# Spannungsversorgung-3.net
KiCad netlist of a schematic drawn in EAGLE
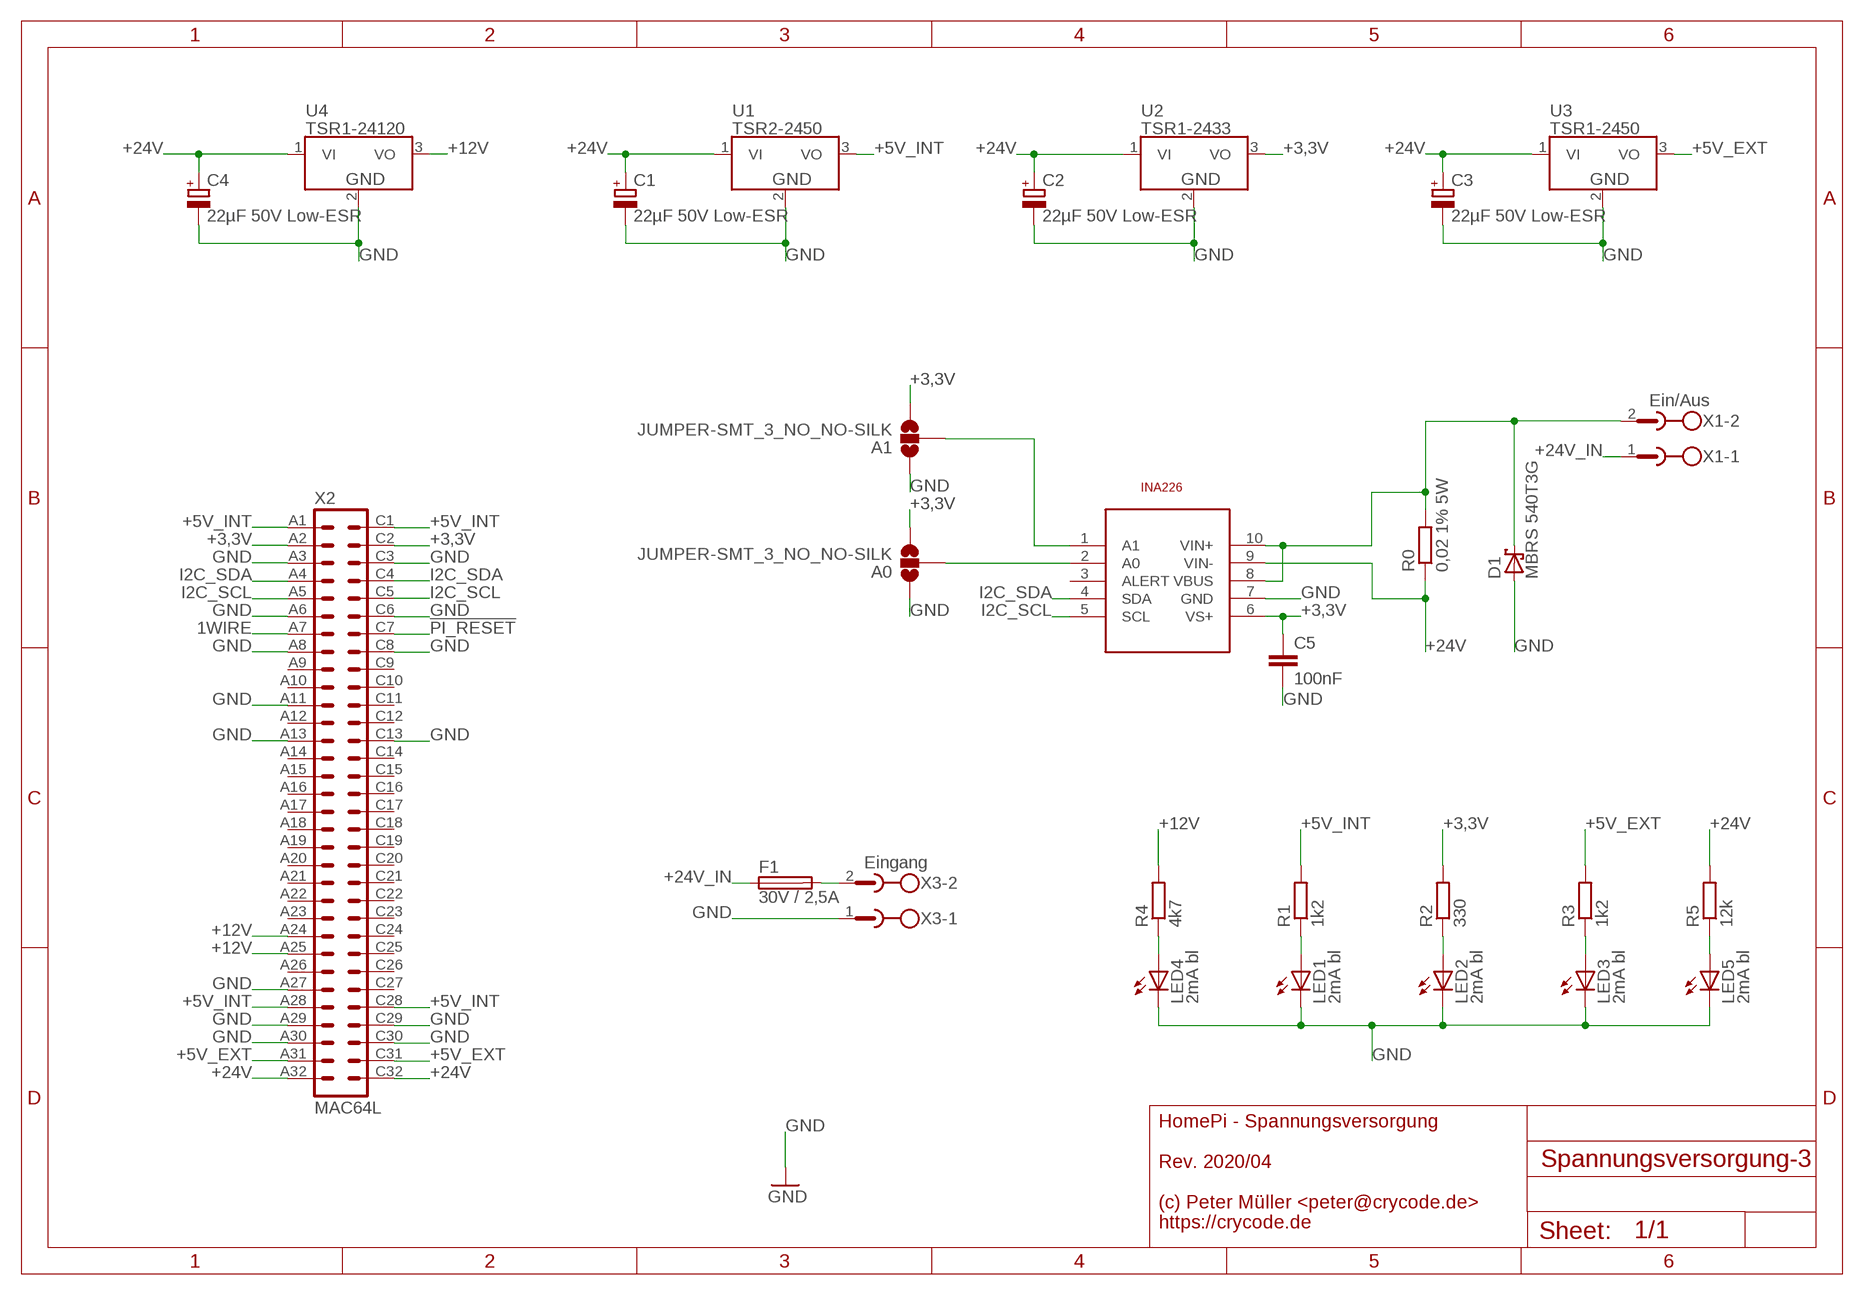
[diagram p0: schematic, sheet 1]

(export (version "E")
  (design (tool "Eeschema 10.0.6"))
  (components
    (comp (ref "A0")
      (value "JUMPER-SMT_3_NO_NO-SILK")
      (footprint "eagle-import:SMT-JUMPER_3_NO_NO-SILK")
      (libsource (lib "eagle-import") (part "JUMPER-SMT_3_NO_NO-SILK"))
    )
    (comp (ref "A1")
      (value "JUMPER-SMT_3_NO_NO-SILK")
      (footprint "eagle-import:SMT-JUMPER_3_NO_NO-SILK")
      (libsource (lib "eagle-import") (part "JUMPER-SMT_3_NO_NO-SILK"))
    )
    (comp (ref "C1")
      (value "22µF 50V Low-ESR")
      (footprint "eagle-import:E2-5")
      (libsource (lib "eagle-import") (part "CPOL-EUE2-5"))
    )
    (comp (ref "C2")
      (value "22µF 50V Low-ESR")
      (footprint "eagle-import:E2-5")
      (libsource (lib "eagle-import") (part "CPOL-EUE2-5"))
    )
    (comp (ref "C3")
      (value "22µF 50V Low-ESR")
      (footprint "eagle-import:E2-5")
      (libsource (lib "eagle-import") (part "CPOL-EUE2-5"))
    )
    (comp (ref "C4")
      (value "22µF 50V Low-ESR")
      (footprint "eagle-import:E2-5")
      (libsource (lib "eagle-import") (part "CPOL-EUE2-5"))
    )
    (comp (ref "C5")
      (value "100nF")
      (footprint "eagle-import:C1206")
      (libsource (lib "eagle-import") (part "C-EUC1206"))
    )
    (comp (ref "D1")
      (value "MBRS 540T3G")
      (footprint "eagle-import:SMC")
      (libsource (lib "eagle-import") (part "SCHOTTKY-DIODESMC"))
    )
    (comp (ref "F1")
      (value "30V / 2,5A")
      (footprint "eagle-import:LITTLEFUSE")
      (libsource (lib "eagle-import") (part "LITTLEFUSE"))
    )
    (comp (ref "IC1")
      (value "TI-INA226")
      (footprint "eagle-import:TI-INA226")
      (libsource (lib "eagle-import") (part "TI-INA226"))
    )
    (comp (ref "LED1")
      (value "2mA bl")
      (footprint "eagle-import:CHIPLED_1206")
      (libsource (lib "eagle-import") (part "LEDCHIPLED_1206"))
    )
    (comp (ref "LED2")
      (value "2mA bl")
      (footprint "eagle-import:CHIPLED_1206")
      (libsource (lib "eagle-import") (part "LEDCHIPLED_1206"))
    )
    (comp (ref "LED3")
      (value "2mA bl")
      (footprint "eagle-import:CHIPLED_1206")
      (libsource (lib "eagle-import") (part "LEDCHIPLED_1206"))
    )
    (comp (ref "LED4")
      (value "2mA bl")
      (footprint "eagle-import:CHIPLED_1206")
      (libsource (lib "eagle-import") (part "LEDCHIPLED_1206"))
    )
    (comp (ref "LED5")
      (value "2mA bl")
      (footprint "eagle-import:CHIPLED_1206")
      (libsource (lib "eagle-import") (part "LEDCHIPLED_1206"))
    )
    (comp (ref "R0")
      (value "0,02 1% 5W")
      (footprint "eagle-import:R2512")
      (libsource (lib "eagle-import") (part "R-EU_R2512"))
    )
    (comp (ref "R1")
      (value "1k2")
      (footprint "eagle-import:R1206")
      (libsource (lib "eagle-import") (part "R-EU_R1206"))
    )
    (comp (ref "R2")
      (value "330")
      (footprint "eagle-import:R1206")
      (libsource (lib "eagle-import") (part "R-EU_R1206"))
    )
    (comp (ref "R3")
      (value "1k2")
      (footprint "eagle-import:R1206")
      (libsource (lib "eagle-import") (part "R-EU_R1206"))
    )
    (comp (ref "R4")
      (value "4k7")
      (footprint "eagle-import:R1206")
      (libsource (lib "eagle-import") (part "R-EU_R1206"))
    )
    (comp (ref "R5")
      (value "12k")
      (footprint "eagle-import:R1206")
      (libsource (lib "eagle-import") (part "R-EU_R1206"))
    )
    (comp (ref "U1")
      (value "TSR2-2450")
      (footprint "eagle-import:TSR2")
      (libsource (lib "eagle-import") (part "TSR2-2450"))
    )
    (comp (ref "U2")
      (value "TSR1-2433")
      (footprint "eagle-import:TSR1")
      (libsource (lib "eagle-import") (part "TSR1-2433"))
    )
    (comp (ref "U3")
      (value "TSR1-2450")
      (footprint "eagle-import:TSR1")
      (libsource (lib "eagle-import") (part "TSR1-2450"))
    )
    (comp (ref "U4")
      (value "TSR1-24120")
      (footprint "eagle-import:TSR1")
      (libsource (lib "eagle-import") (part "TSR1-24120"))
    )
    (comp (ref "X1")
      (value "Ein/Aus")
      (footprint "eagle-import:MSTBA2")
      (fields (field (name "MF") "FARNELL") (field (name "MPN") "1757242"))
      (libsource (lib "eagle-import") (part "MSTBA2"))
    )
    (comp (ref "X2")
      (value "MAC64L")
      (footprint "eagle-import:MAC64L")
      (libsource (lib "eagle-import") (part "MAC64L"))
    )
    (comp (ref "X3")
      (value "Eingang")
      (footprint "eagle-import:MSTBA2")
      (fields (field (name "MF") "FARNELL") (field (name "MPN") "1757242"))
      (libsource (lib "eagle-import") (part "MSTBA2"))
    )
  )
  (nets
    (net (code "1") (name "/+3,3V") (class "Default")
      (node (ref "A0") (pin "3") (pinfunction "3_3") (pintype "passive"))
      (node (ref "A1") (pin "3") (pinfunction "3_3") (pintype "passive"))
      (node (ref "C5") (pin "1") (pinfunction "1_1") (pintype "passive"))
      (node (ref "IC1") (pin "6") (pinfunction "VS+_6") (pintype "bidirectional"))
      (node (ref "R2") (pin "2") (pinfunction "2_2") (pintype "passive"))
      (node (ref "U2") (pin "3") (pinfunction "VO_3") (pintype "power_in"))
      (node (ref "X2") (pin "A2") (pinfunction "A2_A2") (pintype "passive"))
      (node (ref "X2") (pin "C2") (pinfunction "C2_C2") (pintype "passive"))
    )
    (net (code "2") (name "/+5V_EXT") (class "Default")
      (node (ref "R3") (pin "2") (pinfunction "2_2") (pintype "passive"))
      (node (ref "U3") (pin "3") (pinfunction "VO_3") (pintype "power_in"))
      (node (ref "X2") (pin "A31") (pinfunction "A31_A31") (pintype "passive"))
      (node (ref "X2") (pin "C31") (pinfunction "C31_C31") (pintype "passive"))
    )
    (net (code "3") (name "/+5V_INT") (class "Default")
      (node (ref "R1") (pin "2") (pinfunction "2_2") (pintype "passive"))
      (node (ref "U1") (pin "3") (pinfunction "VO_3") (pintype "power_in"))
      (node (ref "X2") (pin "A1") (pinfunction "A1_A1") (pintype "passive"))
      (node (ref "X2") (pin "A28") (pinfunction "A28_A28") (pintype "passive"))
      (node (ref "X2") (pin "C1") (pinfunction "C1_C1") (pintype "passive"))
      (node (ref "X2") (pin "C28") (pinfunction "C28_C28") (pintype "passive"))
    )
    (net (code "4") (name "/+12V") (class "Default")
      (node (ref "R4") (pin "2") (pinfunction "2_2") (pintype "passive"))
      (node (ref "U4") (pin "3") (pinfunction "VO_3") (pintype "power_in"))
      (node (ref "X2") (pin "A24") (pinfunction "A24_A24") (pintype "passive"))
      (node (ref "X2") (pin "A25") (pinfunction "A25_A25") (pintype "passive"))
    )
    (net (code "5") (name "/+24V") (class "Default")
      (node (ref "C1") (pin "+") (pinfunction "+_+") (pintype "passive"))
      (node (ref "C2") (pin "+") (pinfunction "+_+") (pintype "passive"))
      (node (ref "C3") (pin "+") (pinfunction "+_+") (pintype "passive"))
      (node (ref "C4") (pin "+") (pinfunction "+_+") (pintype "passive"))
      (node (ref "IC1") (pin "9") (pinfunction "VIN-_9") (pintype "bidirectional"))
      (node (ref "R0") (pin "1") (pinfunction "1_1") (pintype "passive"))
      (node (ref "R5") (pin "2") (pinfunction "2_2") (pintype "passive"))
      (node (ref "U1") (pin "1") (pinfunction "VI_1") (pintype "power_in"))
      (node (ref "U2") (pin "1") (pinfunction "VI_1") (pintype "power_in"))
      (node (ref "U3") (pin "1") (pinfunction "VI_1") (pintype "power_in"))
      (node (ref "U4") (pin "1") (pinfunction "VI_1") (pintype "power_in"))
      (node (ref "X2") (pin "A32") (pinfunction "A32_A32") (pintype "passive"))
      (node (ref "X2") (pin "C32") (pinfunction "C32_C32") (pintype "passive"))
    )
    (net (code "6") (name "/+24V_IN") (class "Default")
      (node (ref "F1") (pin "1") (pinfunction "1_1") (pintype "passive"))
      (node (ref "X1") (pin "1") (pinfunction "1_1") (pintype "passive"))
    )
    (net (code "7") (name "/1WIRE") (class "Default")
      (node (ref "X2") (pin "A7") (pinfunction "A7_A7") (pintype "passive"))
    )
    (net (code "8") (name "/I2C_SCL") (class "Default")
      (node (ref "IC1") (pin "5") (pinfunction "SCL_5") (pintype "bidirectional"))
      (node (ref "X2") (pin "A5") (pinfunction "A5_A5") (pintype "passive"))
      (node (ref "X2") (pin "C5") (pinfunction "C5_C5") (pintype "passive"))
    )
    (net (code "9") (name "/I2C_SDA") (class "Default")
      (node (ref "IC1") (pin "4") (pinfunction "SDA_4") (pintype "bidirectional"))
      (node (ref "X2") (pin "A4") (pinfunction "A4_A4") (pintype "passive"))
      (node (ref "X2") (pin "C4") (pinfunction "C4_C4") (pintype "passive"))
    )
    (net (code "10") (name "/~{PI_RESET}") (class "Default")
      (node (ref "X2") (pin "C7") (pinfunction "C7_C7") (pintype "passive"))
    )
    (net (code "11") (name "GND") (class "Default")
      (node (ref "A0") (pin "1") (pinfunction "1_1") (pintype "passive"))
      (node (ref "A1") (pin "1") (pinfunction "1_1") (pintype "passive"))
      (node (ref "C1") (pin "-") (pinfunction "-_-") (pintype "passive"))
      (node (ref "C2") (pin "-") (pinfunction "-_-") (pintype "passive"))
      (node (ref "C3") (pin "-") (pinfunction "-_-") (pintype "passive"))
      (node (ref "C4") (pin "-") (pinfunction "-_-") (pintype "passive"))
      (node (ref "C5") (pin "2") (pinfunction "2_2") (pintype "passive"))
      (node (ref "D1") (pin "A") (pinfunction "A_A") (pintype "passive"))
      (node (ref "IC1") (pin "7") (pinfunction "GND_7") (pintype "bidirectional"))
      (node (ref "LED1") (pin "C") (pinfunction "C_C") (pintype "passive"))
      (node (ref "LED2") (pin "C") (pinfunction "C_C") (pintype "passive"))
      (node (ref "LED3") (pin "C") (pinfunction "C_C") (pintype "passive"))
      (node (ref "LED4") (pin "C") (pinfunction "C_C") (pintype "passive"))
      (node (ref "LED5") (pin "C") (pinfunction "C_C") (pintype "passive"))
      (node (ref "U1") (pin "2") (pinfunction "GND_2") (pintype "power_in"))
      (node (ref "U2") (pin "2") (pinfunction "GND_2") (pintype "power_in"))
      (node (ref "U3") (pin "2") (pinfunction "GND_2") (pintype "power_in"))
      (node (ref "U4") (pin "2") (pinfunction "GND_2") (pintype "power_in"))
      (node (ref "X2") (pin "A11") (pinfunction "A11_A11") (pintype "passive"))
      (node (ref "X2") (pin "A13") (pinfunction "A13_A13") (pintype "passive"))
      (node (ref "X2") (pin "A27") (pinfunction "A27_A27") (pintype "passive"))
      (node (ref "X2") (pin "A29") (pinfunction "A29_A29") (pintype "passive"))
      (node (ref "X2") (pin "A3") (pinfunction "A3_A3") (pintype "passive"))
      (node (ref "X2") (pin "A30") (pinfunction "A30_A30") (pintype "passive"))
      (node (ref "X2") (pin "A6") (pinfunction "A6_A6") (pintype "passive"))
      (node (ref "X2") (pin "A8") (pinfunction "A8_A8") (pintype "passive"))
      (node (ref "X2") (pin "C13") (pinfunction "C13_C13") (pintype "passive"))
      (node (ref "X2") (pin "C29") (pinfunction "C29_C29") (pintype "passive"))
      (node (ref "X2") (pin "C3") (pinfunction "C3_C3") (pintype "passive"))
      (node (ref "X2") (pin "C30") (pinfunction "C30_C30") (pintype "passive"))
      (node (ref "X2") (pin "C6") (pinfunction "C6_C6") (pintype "passive"))
      (node (ref "X2") (pin "C8") (pinfunction "C8_C8") (pintype "passive"))
      (node (ref "X3") (pin "1") (pinfunction "1_1") (pintype "passive"))
    )
    (net (code "12") (name "Net-(IC1-A0)") (class "Default")
      (node (ref "A0") (pin "2") (pinfunction "2_2") (pintype "passive"))
      (node (ref "IC1") (pin "2") (pinfunction "A0_2") (pintype "bidirectional"))
    )
    (net (code "13") (name "Net-(IC1-A1)") (class "Default")
      (node (ref "A1") (pin "2") (pinfunction "2_2") (pintype "passive"))
      (node (ref "IC1") (pin "1") (pinfunction "A1_1") (pintype "bidirectional"))
    )
    (net (code "14") (name "Net-(IC1-VBUS)") (class "Default")
      (node (ref "D1") (pin "C") (pinfunction "C_C") (pintype "passive"))
      (node (ref "IC1") (pin "10") (pinfunction "VIN+_10") (pintype "bidirectional"))
      (node (ref "IC1") (pin "8") (pinfunction "VBUS_8") (pintype "bidirectional"))
      (node (ref "R0") (pin "2") (pinfunction "2_2") (pintype "passive"))
      (node (ref "X1") (pin "2") (pinfunction "1_2") (pintype "passive"))
    )
    (net (code "15") (name "Net-(LED1-PadA)") (class "Default")
      (node (ref "LED1") (pin "A") (pinfunction "A_A") (pintype "passive"))
      (node (ref "R1") (pin "1") (pinfunction "1_1") (pintype "passive"))
    )
    (net (code "16") (name "Net-(LED2-PadA)") (class "Default")
      (node (ref "LED2") (pin "A") (pinfunction "A_A") (pintype "passive"))
      (node (ref "R2") (pin "1") (pinfunction "1_1") (pintype "passive"))
    )
    (net (code "17") (name "Net-(LED3-PadA)") (class "Default")
      (node (ref "LED3") (pin "A") (pinfunction "A_A") (pintype "passive"))
      (node (ref "R3") (pin "1") (pinfunction "1_1") (pintype "passive"))
    )
    (net (code "18") (name "Net-(LED4-PadA)") (class "Default")
      (node (ref "LED4") (pin "A") (pinfunction "A_A") (pintype "passive"))
      (node (ref "R4") (pin "1") (pinfunction "1_1") (pintype "passive"))
    )
    (net (code "19") (name "Net-(LED5-PadA)") (class "Default")
      (node (ref "LED5") (pin "A") (pinfunction "A_A") (pintype "passive"))
      (node (ref "R5") (pin "1") (pinfunction "1_1") (pintype "passive"))
    )
    (net (code "20") (name "Net-(X3B-1)") (class "Default")
      (node (ref "F1") (pin "2") (pinfunction "2_2") (pintype "passive"))
      (node (ref "X3") (pin "2") (pinfunction "1_2") (pintype "passive"))
    )
    (net (code "21") (name "unconnected-(IC1-ALERT-Pad3)") (class "Default")
      (node (ref "IC1") (pin "3") (pinfunction "ALERT_3") (pintype "bidirectional"))
    )
    (net (code "22") (name "unconnected-(X2-PadA9)") (class "Default")
      (node (ref "X2") (pin "A9") (pinfunction "A9_A9") (pintype "passive"))
    )
    (net (code "23") (name "unconnected-(X2-PadA10)") (class "Default")
      (node (ref "X2") (pin "A10") (pinfunction "A10_A10") (pintype "passive"))
    )
    (net (code "24") (name "unconnected-(X2-PadA12)") (class "Default")
      (node (ref "X2") (pin "A12") (pinfunction "A12_A12") (pintype "passive"))
    )
    (net (code "25") (name "unconnected-(X2-PadA14)") (class "Default")
      (node (ref "X2") (pin "A14") (pinfunction "A14_A14") (pintype "passive"))
    )
    (net (code "26") (name "unconnected-(X2-PadA15)") (class "Default")
      (node (ref "X2") (pin "A15") (pinfunction "A15_A15") (pintype "passive"))
    )
    (net (code "27") (name "unconnected-(X2-PadA16)") (class "Default")
      (node (ref "X2") (pin "A16") (pinfunction "A16_A16") (pintype "passive"))
    )
    (net (code "28") (name "unconnected-(X2-PadA17)") (class "Default")
      (node (ref "X2") (pin "A17") (pinfunction "A17_A17") (pintype "passive"))
    )
    (net (code "29") (name "unconnected-(X2-PadA18)") (class "Default")
      (node (ref "X2") (pin "A18") (pinfunction "A18_A18") (pintype "passive"))
    )
    (net (code "30") (name "unconnected-(X2-PadA19)") (class "Default")
      (node (ref "X2") (pin "A19") (pinfunction "A19_A19") (pintype "passive"))
    )
    (net (code "31") (name "unconnected-(X2-PadA20)") (class "Default")
      (node (ref "X2") (pin "A20") (pinfunction "A20_A20") (pintype "passive"))
    )
    (net (code "32") (name "unconnected-(X2-PadA21)") (class "Default")
      (node (ref "X2") (pin "A21") (pinfunction "A21_A21") (pintype "passive"))
    )
    (net (code "33") (name "unconnected-(X2-PadA22)") (class "Default")
      (node (ref "X2") (pin "A22") (pinfunction "A22_A22") (pintype "passive"))
    )
    (net (code "34") (name "unconnected-(X2-PadA23)") (class "Default")
      (node (ref "X2") (pin "A23") (pinfunction "A23_A23") (pintype "passive"))
    )
    (net (code "35") (name "unconnected-(X2-PadA26)") (class "Default")
      (node (ref "X2") (pin "A26") (pinfunction "A26_A26") (pintype "passive"))
    )
    (net (code "36") (name "unconnected-(X2-PadC9)") (class "Default")
      (node (ref "X2") (pin "C9") (pinfunction "C9_C9") (pintype "passive"))
    )
    (net (code "37") (name "unconnected-(X2-PadC10)") (class "Default")
      (node (ref "X2") (pin "C10") (pinfunction "C10_C10") (pintype "passive"))
    )
    (net (code "38") (name "unconnected-(X2-PadC11)") (class "Default")
      (node (ref "X2") (pin "C11") (pinfunction "C11_C11") (pintype "passive"))
    )
    (net (code "39") (name "unconnected-(X2-PadC12)") (class "Default")
      (node (ref "X2") (pin "C12") (pinfunction "C12_C12") (pintype "passive"))
    )
    (net (code "40") (name "unconnected-(X2-PadC14)") (class "Default")
      (node (ref "X2") (pin "C14") (pinfunction "C14_C14") (pintype "passive"))
    )
    (net (code "41") (name "unconnected-(X2-PadC15)") (class "Default")
      (node (ref "X2") (pin "C15") (pinfunction "C15_C15") (pintype "passive"))
    )
    (net (code "42") (name "unconnected-(X2-PadC16)") (class "Default")
      (node (ref "X2") (pin "C16") (pinfunction "C16_C16") (pintype "passive"))
    )
    (net (code "43") (name "unconnected-(X2-PadC17)") (class "Default")
      (node (ref "X2") (pin "C17") (pinfunction "C17_C17") (pintype "passive"))
    )
    (net (code "44") (name "unconnected-(X2-PadC18)") (class "Default")
      (node (ref "X2") (pin "C18") (pinfunction "C18_C18") (pintype "passive"))
    )
    (net (code "45") (name "unconnected-(X2-PadC19)") (class "Default")
      (node (ref "X2") (pin "C19") (pinfunction "C19_C19") (pintype "passive"))
    )
    (net (code "46") (name "unconnected-(X2-PadC20)") (class "Default")
      (node (ref "X2") (pin "C20") (pinfunction "C20_C20") (pintype "passive"))
    )
    (net (code "47") (name "unconnected-(X2-PadC21)") (class "Default")
      (node (ref "X2") (pin "C21") (pinfunction "C21_C21") (pintype "passive"))
    )
    (net (code "48") (name "unconnected-(X2-PadC22)") (class "Default")
      (node (ref "X2") (pin "C22") (pinfunction "C22_C22") (pintype "passive"))
    )
    (net (code "49") (name "unconnected-(X2-PadC23)") (class "Default")
      (node (ref "X2") (pin "C23") (pinfunction "C23_C23") (pintype "passive"))
    )
    (net (code "50") (name "unconnected-(X2-PadC24)") (class "Default")
      (node (ref "X2") (pin "C24") (pinfunction "C24_C24") (pintype "passive"))
    )
    (net (code "51") (name "unconnected-(X2-PadC25)") (class "Default")
      (node (ref "X2") (pin "C25") (pinfunction "C25_C25") (pintype "passive"))
    )
    (net (code "52") (name "unconnected-(X2-PadC26)") (class "Default")
      (node (ref "X2") (pin "C26") (pinfunction "C26_C26") (pintype "passive"))
    )
    (net (code "53") (name "unconnected-(X2-PadC27)") (class "Default")
      (node (ref "X2") (pin "C27") (pinfunction "C27_C27") (pintype "passive"))
    )
  )
)
